# 003_LCDdriver.net
KiCad netlist of a schematic drawn in EAGLE
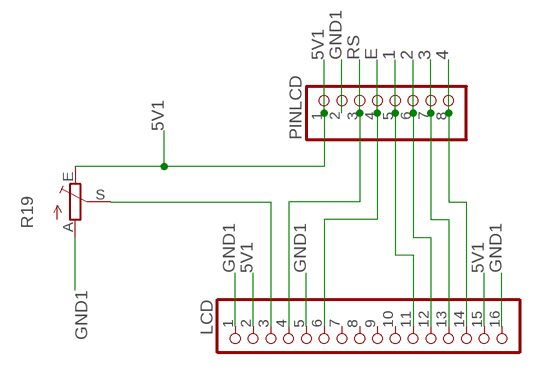
[diagram p0: schematic, sheet 1]

(export (version "E")
  (design (tool "Eeschema 10.0.6"))
  (components
    (comp (ref "LCD")
      (value "PINHD-1X16")
      (footprint "eagle-import:1X16")
      (libsource (lib "eagle-import") (part "PINHD-1X16"))
    )
    (comp (ref "PINLCD")
      (value "PINHD-1X8")
      (footprint "eagle-import:1X08")
      (libsource (lib "eagle-import") (part "PINHD-1X8"))
    )
    (comp (ref "R19")
      (value "TRIM_EU-B25U")
      (footprint "eagle-import:B25U")
      (libsource (lib "eagle-import") (part "TRIM_EU-B25U"))
    )
  )
  (nets
    (net (code "1") (name "/1") (class "Default")
      (node (ref "LCD") (pin "11") (pinfunction "11_11") (pintype "passive"))
      (node (ref "PINLCD") (pin "5") (pinfunction "5_5") (pintype "passive"))
    )
    (net (code "2") (name "/2") (class "Default")
      (node (ref "LCD") (pin "12") (pinfunction "12_12") (pintype "passive"))
      (node (ref "PINLCD") (pin "6") (pinfunction "6_6") (pintype "passive"))
    )
    (net (code "3") (name "/3") (class "Default")
      (node (ref "LCD") (pin "13") (pinfunction "13_13") (pintype "passive"))
      (node (ref "PINLCD") (pin "7") (pinfunction "7_7") (pintype "passive"))
    )
    (net (code "4") (name "/4") (class "Default")
      (node (ref "LCD") (pin "14") (pinfunction "14_14") (pintype "passive"))
      (node (ref "PINLCD") (pin "8") (pinfunction "8_8") (pintype "passive"))
    )
    (net (code "5") (name "/5V1") (class "Default")
      (node (ref "LCD") (pin "15") (pinfunction "15_15") (pintype "passive"))
      (node (ref "LCD") (pin "2") (pinfunction "2_2") (pintype "passive"))
      (node (ref "PINLCD") (pin "1") (pinfunction "1_1") (pintype "passive"))
      (node (ref "R19") (pin "E") (pinfunction "E_E") (pintype "passive"))
    )
    (net (code "6") (name "/E") (class "Default")
      (node (ref "LCD") (pin "6") (pinfunction "6_6") (pintype "passive"))
      (node (ref "PINLCD") (pin "4") (pinfunction "4_4") (pintype "passive"))
    )
    (net (code "7") (name "/GND1") (class "Default")
      (node (ref "LCD") (pin "1") (pinfunction "1_1") (pintype "passive"))
      (node (ref "LCD") (pin "16") (pinfunction "16_16") (pintype "passive"))
      (node (ref "LCD") (pin "5") (pinfunction "5_5") (pintype "passive"))
      (node (ref "PINLCD") (pin "2") (pinfunction "2_2") (pintype "passive"))
      (node (ref "R19") (pin "A") (pinfunction "A_A") (pintype "passive"))
    )
    (net (code "8") (name "/RS") (class "Default")
      (node (ref "LCD") (pin "4") (pinfunction "4_4") (pintype "passive"))
      (node (ref "PINLCD") (pin "3") (pinfunction "3_3") (pintype "passive"))
    )
    (net (code "9") (name "Net-(LCD-Pad3)") (class "Default")
      (node (ref "LCD") (pin "3") (pinfunction "3_3") (pintype "passive"))
      (node (ref "R19") (pin "S") (pinfunction "S_S") (pintype "passive"))
    )
    (net (code "10") (name "unconnected-(LCD-Pad7)") (class "Default")
      (node (ref "LCD") (pin "7") (pinfunction "7_7") (pintype "passive"))
    )
    (net (code "11") (name "unconnected-(LCD-Pad8)") (class "Default")
      (node (ref "LCD") (pin "8") (pinfunction "8_8") (pintype "passive"))
    )
    (net (code "12") (name "unconnected-(LCD-Pad9)") (class "Default")
      (node (ref "LCD") (pin "9") (pinfunction "9_9") (pintype "passive"))
    )
    (net (code "13") (name "unconnected-(LCD-Pad10)") (class "Default")
      (node (ref "LCD") (pin "10") (pinfunction "10_10") (pintype "passive"))
    )
  )
)
